# HL_Interface_pcb.net
KiCad netlist of a schematic drawn in EAGLE
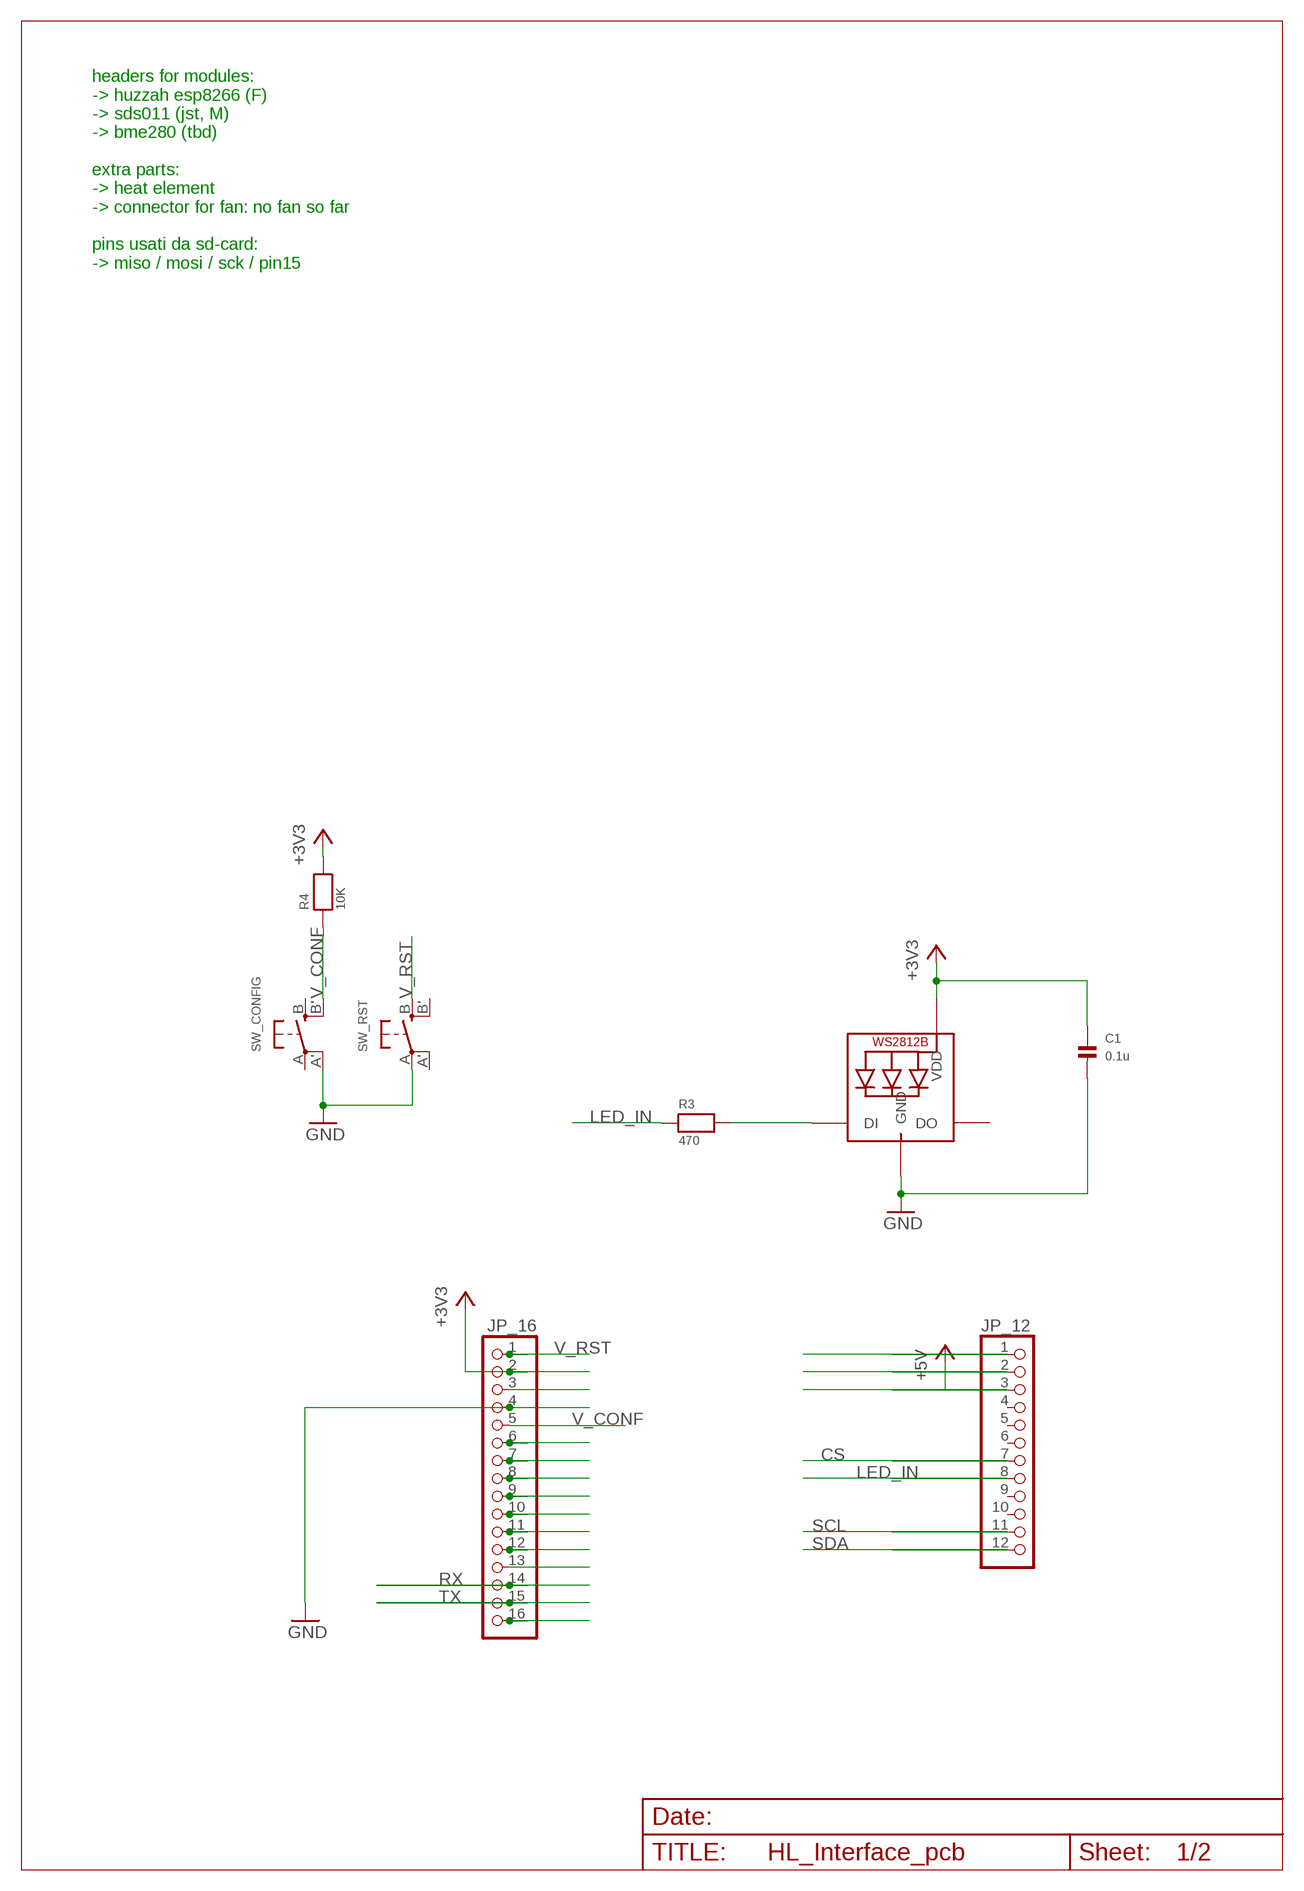
[diagram p0: schematic, sheet 1]

(export (version "E")
  (design (tool "Eeschema 10.0.6"))
  (components
    (comp (ref "C1")
      (value "0.1u")
      (footprint "eagle-import:1206")
      (libsource (lib "eagle-import") (part "CAP_CERAMIC1206"))
    )
    (comp (ref "JP_12")
      (value "HEADER-1X12OVAL")
      (footprint "eagle-import:1X12_OVAL")
      (libsource (lib "eagle-import") (part "HEADER-1X12OVAL"))
    )
    (comp (ref "JP_16")
      (value "HEADER-1X16")
      (footprint "eagle-import:1X16_OVAL")
      (libsource (lib "eagle-import") (part "HEADER-1X16"))
    )
    (comp (ref "LED")
      (value "WS2812B5050")
      (footprint "eagle-import:WS2812B")
      (libsource (lib "eagle-import") (part "WS2812B5050"))
    )
    (comp (ref "R3")
      (value "470")
      (footprint "eagle-import:1206")
      (libsource (lib "eagle-import") (part "RESISTOR1206"))
    )
    (comp (ref "R4")
      (value "10K")
      (footprint "eagle-import:1206")
      (libsource (lib "eagle-import") (part "RESISTOR1206"))
    )
    (comp (ref "SW_CONFIG")
      (value "SWITCH_TACT_SMT")
      (footprint "eagle-import:EVQ-Q2")
      (libsource (lib "eagle-import") (part "SWITCH_TACT_SMT"))
    )
    (comp (ref "SW_RST")
      (value "SWITCH_TACT_SMT")
      (footprint "eagle-import:EVQ-Q2")
      (libsource (lib "eagle-import") (part "SWITCH_TACT_SMT"))
    )
  )
  (nets
    (net (code "1") (name "+3V3") (class "Default")
      (node (ref "C1") (pin "1") (pinfunction "P$1_1") (pintype "passive"))
      (node (ref "JP_16") (pin "2") (pinfunction "2_2") (pintype "passive"))
      (node (ref "LED") (pin "1-VDD") (pinfunction "VDD_1-VDD") (pintype "power_in"))
      (node (ref "R4") (pin "2") (pinfunction "2_2") (pintype "passive"))
    )
    (net (code "2") (name "+5V") (class "Default")
      (node (ref "JP_12") (pin "3") (pinfunction "3_3") (pintype "passive"))
    )
    (net (code "3") (name "CS") (class "Default")
      (node (ref "JP_12") (pin "7") (pinfunction "7_7") (pintype "passive"))
    )
    (net (code "4") (name "GND") (class "Default")
      (node (ref "C1") (pin "2") (pinfunction "P$2_2") (pintype "passive"))
      (node (ref "JP_16") (pin "4") (pinfunction "4_4") (pintype "passive"))
      (node (ref "LED") (pin "3-GND") (pinfunction "GND_3-GND") (pintype "power_in"))
      (node (ref "SW_CONFIG") (pin "A'") (pinfunction "P1_A'") (pintype "passive"))
      (node (ref "SW_RST") (pin "A") (pinfunction "P_A") (pintype "passive"))
    )
    (net (code "5") (name "LED_IN") (class "Default")
      (node (ref "JP_12") (pin "8") (pinfunction "8_8") (pintype "passive"))
      (node (ref "R3") (pin "1") (pinfunction "1_1") (pintype "passive"))
    )
    (net (code "6") (name "Net-(LED-DI)") (class "Default")
      (node (ref "LED") (pin "4-DIN") (pinfunction "DI_4-DIN") (pintype "input"))
      (node (ref "R3") (pin "2") (pinfunction "2_2") (pintype "passive"))
    )
    (net (code "7") (name "RX") (class "Default")
      (node (ref "JP_16") (pin "14") (pinfunction "14_14") (pintype "passive"))
    )
    (net (code "8") (name "SCL") (class "Default")
      (node (ref "JP_12") (pin "11") (pinfunction "11_11") (pintype "passive"))
    )
    (net (code "9") (name "SDA") (class "Default")
      (node (ref "JP_12") (pin "12") (pinfunction "12_12") (pintype "passive"))
    )
    (net (code "10") (name "TX") (class "Default")
      (node (ref "JP_16") (pin "15") (pinfunction "15_15") (pintype "passive"))
    )
    (net (code "11") (name "V_CONF") (class "Default")
      (node (ref "JP_16") (pin "5") (pinfunction "5_5") (pintype "passive"))
      (node (ref "R4") (pin "1") (pinfunction "1_1") (pintype "passive"))
      (node (ref "SW_CONFIG") (pin "B'") (pinfunction "S1_B'") (pintype "passive"))
    )
    (net (code "12") (name "V_RST") (class "Default")
      (node (ref "JP_16") (pin "1") (pinfunction "1_1") (pintype "passive"))
      (node (ref "SW_RST") (pin "B") (pinfunction "S_B") (pintype "passive"))
    )
    (net (code "13") (name "unconnected-(JP_12-Pad1)") (class "Default")
      (node (ref "JP_12") (pin "1") (pinfunction "1_1") (pintype "passive"))
    )
    (net (code "14") (name "unconnected-(JP_12-Pad2)") (class "Default")
      (node (ref "JP_12") (pin "2") (pinfunction "2_2") (pintype "passive"))
    )
    (net (code "15") (name "unconnected-(JP_12-Pad4)") (class "Default")
      (node (ref "JP_12") (pin "4") (pinfunction "4_4") (pintype "passive"))
    )
    (net (code "16") (name "unconnected-(JP_12-Pad5)") (class "Default")
      (node (ref "JP_12") (pin "5") (pinfunction "5_5") (pintype "passive"))
    )
    (net (code "17") (name "unconnected-(JP_12-Pad6)") (class "Default")
      (node (ref "JP_12") (pin "6") (pinfunction "6_6") (pintype "passive"))
    )
    (net (code "18") (name "unconnected-(JP_12-Pad9)") (class "Default")
      (node (ref "JP_12") (pin "9") (pinfunction "9_9") (pintype "passive"))
    )
    (net (code "19") (name "unconnected-(JP_12-Pad10)") (class "Default")
      (node (ref "JP_12") (pin "10") (pinfunction "10_10") (pintype "passive"))
    )
    (net (code "20") (name "unconnected-(JP_16-Pad3)") (class "Default")
      (node (ref "JP_16") (pin "3") (pinfunction "3_3") (pintype "passive"))
    )
    (net (code "21") (name "unconnected-(JP_16-Pad6)") (class "Default")
      (node (ref "JP_16") (pin "6") (pinfunction "6_6") (pintype "passive"))
    )
    (net (code "22") (name "unconnected-(JP_16-Pad7)") (class "Default")
      (node (ref "JP_16") (pin "7") (pinfunction "7_7") (pintype "passive"))
    )
    (net (code "23") (name "unconnected-(JP_16-Pad8)") (class "Default")
      (node (ref "JP_16") (pin "8") (pinfunction "8_8") (pintype "passive"))
    )
    (net (code "24") (name "unconnected-(JP_16-Pad9)") (class "Default")
      (node (ref "JP_16") (pin "9") (pinfunction "9_9") (pintype "passive"))
    )
    (net (code "25") (name "unconnected-(JP_16-Pad10)") (class "Default")
      (node (ref "JP_16") (pin "10") (pinfunction "10_10") (pintype "passive"))
    )
    (net (code "26") (name "unconnected-(JP_16-Pad11)") (class "Default")
      (node (ref "JP_16") (pin "11") (pinfunction "11_11") (pintype "passive"))
    )
    (net (code "27") (name "unconnected-(JP_16-Pad12)") (class "Default")
      (node (ref "JP_16") (pin "12") (pinfunction "12_12") (pintype "passive"))
    )
    (net (code "28") (name "unconnected-(JP_16-Pad13)") (class "Default")
      (node (ref "JP_16") (pin "13") (pinfunction "13_13") (pintype "passive"))
    )
    (net (code "29") (name "unconnected-(JP_16-Pad16)") (class "Default")
      (node (ref "JP_16") (pin "16") (pinfunction "16_16") (pintype "passive"))
    )
    (net (code "30") (name "unconnected-(LED-DO-Pad2-DOUT)") (class "Default")
      (node (ref "LED") (pin "2-DOUT") (pinfunction "DO_2-DOUT") (pintype "output"))
    )
    (net (code "31") (name "unconnected-(SW_CONFIG-P-PadA)") (class "Default")
      (node (ref "SW_CONFIG") (pin "A") (pinfunction "P_A") (pintype "passive"))
    )
    (net (code "32") (name "unconnected-(SW_CONFIG-S-PadB)") (class "Default")
      (node (ref "SW_CONFIG") (pin "B") (pinfunction "S_B") (pintype "passive"))
    )
    (net (code "33") (name "unconnected-(SW_RST-P1-PadA')") (class "Default")
      (node (ref "SW_RST") (pin "A'") (pinfunction "P1_A'") (pintype "passive"))
    )
    (net (code "34") (name "unconnected-(SW_RST-S1-PadB')") (class "Default")
      (node (ref "SW_RST") (pin "B'") (pinfunction "S1_B'") (pintype "passive"))
    )
  )
)
